# 2403_NUCLEO64.net
KiCad netlist of a schematic drawn in Altium Designer
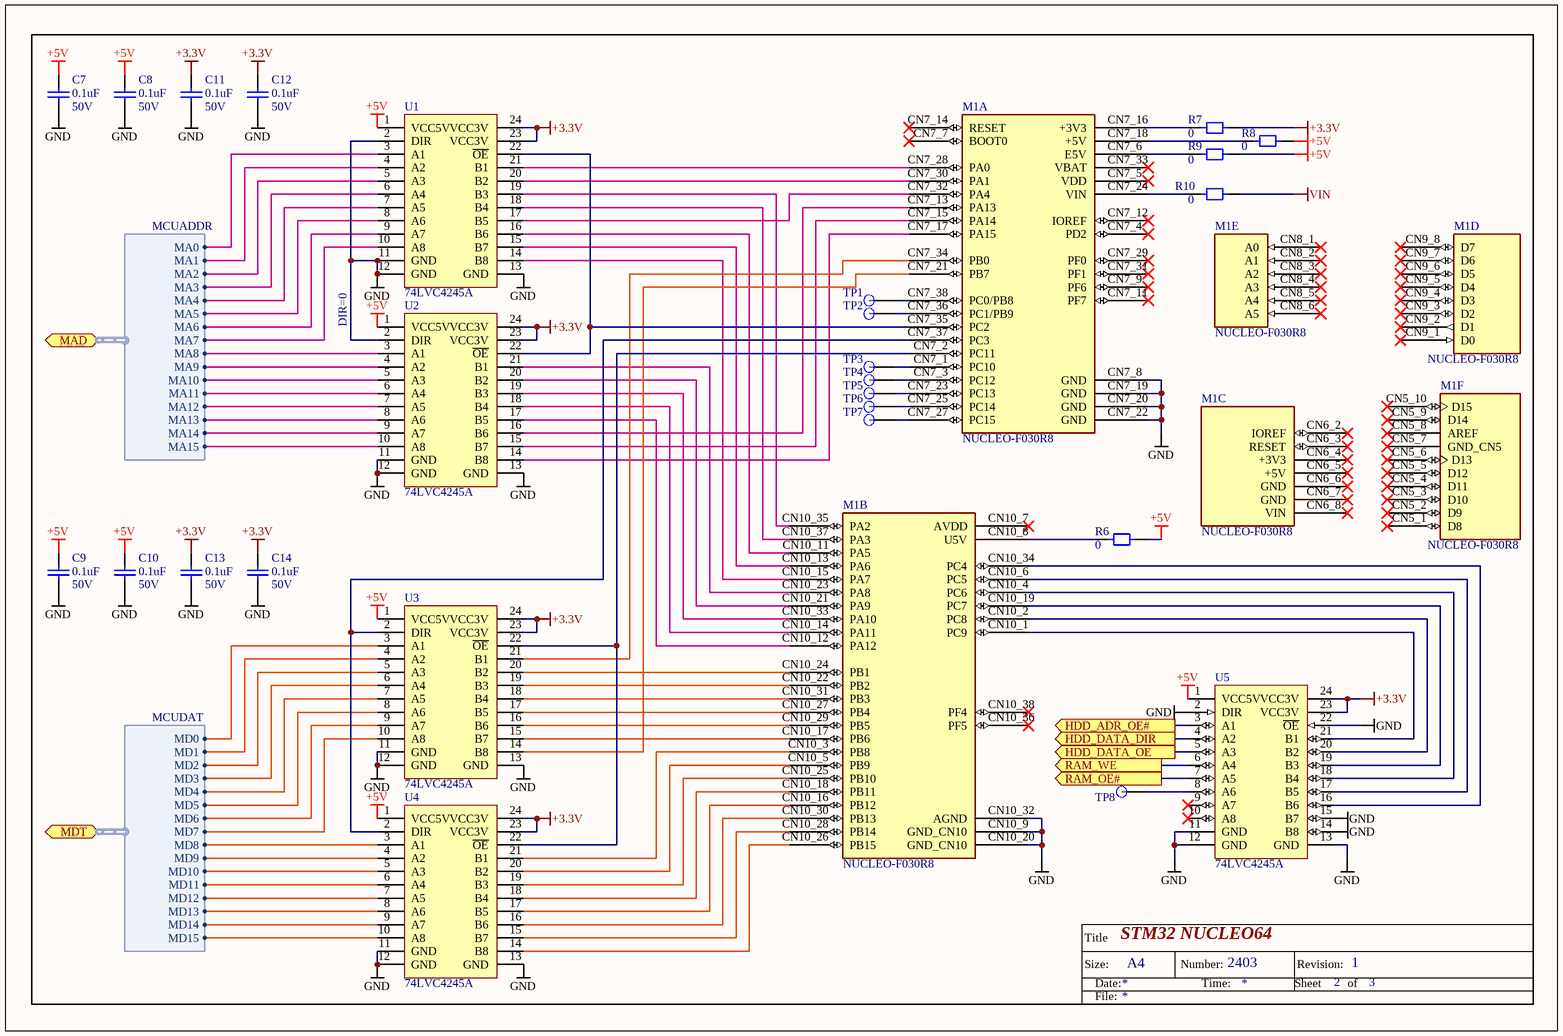
[diagram p0: 2403_NUCLEO64.SchDoc]

(export (version "E")
  (design (tool "Eeschema 10.0.6"))
  (components
    (comp (ref "C7")
      (value "0.1uF")
      (footprint "0805_CAPC2013X100N")
      (description "Capacitor SMD")
      (fields (field (name "RATED VOLTAGE") "50V") (field (name "PUBLISHER") "SY"))
      (libsource (lib "Prj24_Library") (part "Cap SMD"))
    )
    (comp (ref "C8")
      (value "0.1uF")
      (footprint "0805_CAPC2013X100N")
      (description "Capacitor SMD")
      (fields (field (name "RATED VOLTAGE") "50V") (field (name "PUBLISHER") "SY"))
      (libsource (lib "Prj24_Library") (part "Cap SMD"))
    )
    (comp (ref "C9")
      (value "0.1uF")
      (footprint "0805_CAPC2013X100N")
      (description "Capacitor SMD")
      (fields (field (name "RATED VOLTAGE") "50V") (field (name "PUBLISHER") "SY"))
      (libsource (lib "Prj24_Library") (part "Cap SMD"))
    )
    (comp (ref "C10")
      (value "0.1uF")
      (footprint "0805_CAPC2013X100N")
      (description "Capacitor SMD")
      (fields (field (name "RATED VOLTAGE") "50V") (field (name "PUBLISHER") "SY"))
      (libsource (lib "Prj24_Library") (part "Cap SMD"))
    )
    (comp (ref "C11")
      (value "0.1uF")
      (footprint "0805_CAPC2013X100N")
      (description "Capacitor SMD")
      (fields (field (name "RATED VOLTAGE") "50V") (field (name "PUBLISHER") "SY"))
      (libsource (lib "Prj24_Library") (part "Cap SMD"))
    )
    (comp (ref "C12")
      (value "0.1uF")
      (footprint "0805_CAPC2013X100N")
      (description "Capacitor SMD")
      (fields (field (name "RATED VOLTAGE") "50V") (field (name "PUBLISHER") "SY"))
      (libsource (lib "Prj24_Library") (part "Cap SMD"))
    )
    (comp (ref "C13")
      (value "0.1uF")
      (footprint "0805_CAPC2013X100N")
      (description "Capacitor SMD")
      (fields (field (name "RATED VOLTAGE") "50V") (field (name "PUBLISHER") "SY"))
      (libsource (lib "Prj24_Library") (part "Cap SMD"))
    )
    (comp (ref "C14")
      (value "0.1uF")
      (footprint "0805_CAPC2013X100N")
      (description "Capacitor SMD")
      (fields (field (name "RATED VOLTAGE") "50V") (field (name "PUBLISHER") "SY"))
      (libsource (lib "Prj24_Library") (part "Cap SMD"))
    )
    (comp (ref "M1")
      (value "NUCLEO-F030R8")
      (footprint "MODULE_NUCLEO-F030R8")
      (fields (field (name "MF") "STMicroelectronics") (field (name "PUBLISHER") "SY"))
      (libsource (lib "Prj24_Library") (part "NUCLEO-F030R8"))
    )
    (comp (ref "R6")
      (value "0")
      (footprint "0805_RESC2013X84N")
      (description "SMD Resistor")
      (fields (field (name "TOLERANCE") "5%") (field (name "POWER") "0.1W") (field (name "PUBLISHER") "SY"))
      (libsource (lib "Prj24_Library") (part "Resistor SMD L"))
    )
    (comp (ref "R7")
      (value "0")
      (footprint "0805_RESC2013X84N")
      (description "SMD Resistor")
      (fields (field (name "TOLERANCE") "5%") (field (name "POWER") "0.1W") (field (name "PUBLISHER") "SY"))
      (libsource (lib "Prj24_Library") (part "Resistor SMD L"))
    )
    (comp (ref "R8")
      (value "0")
      (footprint "0805_RESC2013X84N")
      (description "SMD Resistor")
      (fields (field (name "TOLERANCE") "5%") (field (name "POWER") "0.1W") (field (name "PUBLISHER") "SY"))
      (libsource (lib "Prj24_Library") (part "Resistor SMD L"))
    )
    (comp (ref "R9")
      (value "0")
      (footprint "0805_RESC2013X84N")
      (description "SMD Resistor")
      (fields (field (name "TOLERANCE") "5%") (field (name "POWER") "0.1W") (field (name "PUBLISHER") "SY"))
      (libsource (lib "Prj24_Library") (part "Resistor SMD L"))
    )
    (comp (ref "R10")
      (value "0")
      (footprint "0805_RESC2013X84N")
      (description "SMD Resistor")
      (fields (field (name "TOLERANCE") "5%") (field (name "POWER") "0.1W") (field (name "PUBLISHER") "SY"))
      (libsource (lib "Prj24_Library") (part "Resistor SMD L"))
    )
    (comp (ref "TP1")
      (value "TEST_POINT")
      (footprint "TEST2")
      (description "Test point")
      (fields (field (name "PUBLISHER") "SY"))
      (libsource (lib "Prj24_Library") (part "TEST_POINT"))
    )
    (comp (ref "TP2")
      (value "TEST_POINT")
      (footprint "TEST2")
      (description "Test point")
      (fields (field (name "PUBLISHER") "SY"))
      (libsource (lib "Prj24_Library") (part "TEST_POINT"))
    )
    (comp (ref "TP3")
      (value "TEST_POINT")
      (footprint "TEST2")
      (description "Test point")
      (fields (field (name "PUBLISHER") "SY"))
      (libsource (lib "Prj24_Library") (part "TEST_POINT"))
    )
    (comp (ref "TP4")
      (value "TEST_POINT")
      (footprint "TEST2")
      (description "Test point")
      (fields (field (name "PUBLISHER") "SY"))
      (libsource (lib "Prj24_Library") (part "TEST_POINT"))
    )
    (comp (ref "TP5")
      (value "TEST_POINT")
      (footprint "TEST2")
      (description "Test point")
      (fields (field (name "PUBLISHER") "SY"))
      (libsource (lib "Prj24_Library") (part "TEST_POINT"))
    )
    (comp (ref "TP6")
      (value "TEST_POINT")
      (footprint "TEST2")
      (description "Test point")
      (fields (field (name "PUBLISHER") "SY"))
      (libsource (lib "Prj24_Library") (part "TEST_POINT"))
    )
    (comp (ref "TP7")
      (value "TEST_POINT")
      (footprint "TEST2")
      (description "Test point")
      (fields (field (name "PUBLISHER") "SY"))
      (libsource (lib "Prj24_Library") (part "TEST_POINT"))
    )
    (comp (ref "TP8")
      (value "TEST_POINT")
      (footprint "TEST2")
      (description "Test point")
      (fields (field (name "PUBLISHER") "SY"))
      (libsource (lib "Prj24_Library") (part "TEST_POINT"))
    )
    (comp (ref "U1")
      (value "74LVC4245A")
      (footprint "SOIC127P1032X265-24N")
      (description "Octal Bus Transceiver and 3.3-V to 5-V Shifter\r\nWith 3-State Outputs")
      (fields (field (name "PUBLISHER") "SY") (field (name "SOURCE") "Renishaw MP12"))
      (libsource (lib "Prj24_Library") (part "74LVC4245A"))
    )
    (comp (ref "U2")
      (value "74LVC4245A")
      (footprint "SOIC127P1032X265-24N")
      (description "Octal Bus Transceiver and 3.3-V to 5-V Shifter\r\nWith 3-State Outputs")
      (fields (field (name "PUBLISHER") "SY") (field (name "SOURCE") "Renishaw MP12"))
      (libsource (lib "Prj24_Library") (part "74LVC4245A"))
    )
    (comp (ref "U3")
      (value "74LVC4245A")
      (footprint "SOIC127P1032X265-24N")
      (description "Octal Bus Transceiver and 3.3-V to 5-V Shifter\r\nWith 3-State Outputs")
      (fields (field (name "PUBLISHER") "SY") (field (name "SOURCE") "Renishaw MP12"))
      (libsource (lib "Prj24_Library") (part "74LVC4245A"))
    )
    (comp (ref "U4")
      (value "74LVC4245A")
      (footprint "SOIC127P1032X265-24N")
      (description "Octal Bus Transceiver and 3.3-V to 5-V Shifter\r\nWith 3-State Outputs")
      (fields (field (name "PUBLISHER") "SY") (field (name "SOURCE") "Renishaw MP12"))
      (libsource (lib "Prj24_Library") (part "74LVC4245A"))
    )
    (comp (ref "U5")
      (value "74LVC4245A")
      (footprint "SOIC127P1032X265-24N")
      (description "Octal Bus Transceiver and 3.3-V to 5-V Shifter\r\nWith 3-State Outputs")
      (fields (field (name "PUBLISHER") "SY") (field (name "SOURCE") "Renishaw MP12"))
      (libsource (lib "Prj24_Library") (part "74LVC4245A"))
    )
  )
  (nets
    (net (code "3") (name "+3.3V") (class "Default")
      (node (ref "C11") (pin "2") (pinfunction "2_2") (pintype "passive"))
      (node (ref "C12") (pin "2") (pinfunction "2_2") (pintype "passive"))
      (node (ref "C13") (pin "2") (pinfunction "2_2") (pintype "passive"))
      (node (ref "C14") (pin "2") (pinfunction "2_2") (pintype "passive"))
      (node (ref "R7") (pin "2") (pinfunction "2_2") (pintype "passive"))
      (node (ref "U1") (pin "23") (pinfunction "VCC3V_23") (pintype "passive"))
      (node (ref "U1") (pin "24") (pinfunction "VCC3V_24") (pintype "passive"))
      (node (ref "U2") (pin "23") (pinfunction "VCC3V_23") (pintype "passive"))
      (node (ref "U2") (pin "24") (pinfunction "VCC3V_24") (pintype "passive"))
      (node (ref "U3") (pin "23") (pinfunction "VCC3V_23") (pintype "passive"))
      (node (ref "U3") (pin "24") (pinfunction "VCC3V_24") (pintype "passive"))
      (node (ref "U4") (pin "23") (pinfunction "VCC3V_23") (pintype "passive"))
      (node (ref "U4") (pin "24") (pinfunction "VCC3V_24") (pintype "passive"))
      (node (ref "U5") (pin "23") (pinfunction "VCC3V_23") (pintype "passive"))
      (node (ref "U5") (pin "24") (pinfunction "VCC3V_24") (pintype "passive"))
    )
    (net (code "4") (name "+5V") (class "Default")
      (node (ref "C10") (pin "2") (pinfunction "2_2") (pintype "passive"))
      (node (ref "C7") (pin "2") (pinfunction "2_2") (pintype "passive"))
      (node (ref "C8") (pin "2") (pinfunction "2_2") (pintype "passive"))
      (node (ref "C9") (pin "2") (pinfunction "2_2") (pintype "passive"))
      (node (ref "R6") (pin "2") (pinfunction "2_2") (pintype "passive"))
      (node (ref "R8") (pin "2") (pinfunction "2_2") (pintype "passive"))
      (node (ref "R9") (pin "2") (pinfunction "2_2") (pintype "passive"))
      (node (ref "U1") (pin "1") (pinfunction "VCC5V_1") (pintype "passive"))
      (node (ref "U2") (pin "1") (pinfunction "VCC5V_1") (pintype "passive"))
      (node (ref "U3") (pin "1") (pinfunction "VCC5V_1") (pintype "passive"))
      (node (ref "U4") (pin "1") (pinfunction "VCC5V_1") (pintype "passive"))
      (node (ref "U5") (pin "1") (pinfunction "VCC5V_1") (pintype "passive"))
    )
    (net (code "5") (name "/HDD_ADR_OE#") (class "Default")
      (node (ref "U5") (pin "3") (pinfunction "A1_3") (pintype "passive"))
    )
    (net (code "6") (name "/HDD_DATA_DIR") (class "Default")
      (node (ref "U5") (pin "4") (pinfunction "A2_4") (pintype "passive"))
    )
    (net (code "7") (name "/HDD_DATA_OE") (class "Default")
      (node (ref "U5") (pin "5") (pinfunction "A3_5") (pintype "passive"))
    )
    (net (code "8") (name "/MA0") (class "Default")
      (node (ref "U1") (pin "3") (pinfunction "A1_3") (pintype "passive"))
    )
    (net (code "9") (name "/MA1") (class "Default")
      (node (ref "U1") (pin "4") (pinfunction "A2_4") (pintype "passive"))
    )
    (net (code "10") (name "/MA2") (class "Default")
      (node (ref "U1") (pin "5") (pinfunction "A3_5") (pintype "passive"))
    )
    (net (code "11") (name "/MA3") (class "Default")
      (node (ref "U1") (pin "6") (pinfunction "A4_6") (pintype "passive"))
    )
    (net (code "12") (name "/MA4") (class "Default")
      (node (ref "U1") (pin "7") (pinfunction "A5_7") (pintype "passive"))
    )
    (net (code "13") (name "/MA5") (class "Default")
      (node (ref "U1") (pin "8") (pinfunction "A6_8") (pintype "passive"))
    )
    (net (code "14") (name "/MA6") (class "Default")
      (node (ref "U1") (pin "9") (pinfunction "A7_9") (pintype "passive"))
    )
    (net (code "15") (name "/MA7") (class "Default")
      (node (ref "U1") (pin "10") (pinfunction "A8_10") (pintype "passive"))
    )
    (net (code "16") (name "/MA8") (class "Default")
      (node (ref "U2") (pin "3") (pinfunction "A1_3") (pintype "passive"))
    )
    (net (code "17") (name "/MA9") (class "Default")
      (node (ref "U2") (pin "4") (pinfunction "A2_4") (pintype "passive"))
    )
    (net (code "18") (name "/MA10") (class "Default")
      (node (ref "U2") (pin "5") (pinfunction "A3_5") (pintype "passive"))
    )
    (net (code "19") (name "/MA11") (class "Default")
      (node (ref "U2") (pin "6") (pinfunction "A4_6") (pintype "passive"))
    )
    (net (code "20") (name "/MA12") (class "Default")
      (node (ref "U2") (pin "7") (pinfunction "A5_7") (pintype "passive"))
    )
    (net (code "21") (name "/MA13") (class "Default")
      (node (ref "U2") (pin "8") (pinfunction "A6_8") (pintype "passive"))
    )
    (net (code "22") (name "/MA14") (class "Default")
      (node (ref "U2") (pin "9") (pinfunction "A7_9") (pintype "passive"))
    )
    (net (code "23") (name "/MA15") (class "Default")
      (node (ref "U2") (pin "10") (pinfunction "A8_10") (pintype "passive"))
    )
    (net (code "24") (name "/MD0") (class "Default")
      (node (ref "U3") (pin "3") (pinfunction "A1_3") (pintype "passive"))
    )
    (net (code "25") (name "/MD1") (class "Default")
      (node (ref "U3") (pin "4") (pinfunction "A2_4") (pintype "passive"))
    )
    (net (code "26") (name "/MD2") (class "Default")
      (node (ref "U3") (pin "5") (pinfunction "A3_5") (pintype "passive"))
    )
    (net (code "27") (name "/MD3") (class "Default")
      (node (ref "U3") (pin "6") (pinfunction "A4_6") (pintype "passive"))
    )
    (net (code "28") (name "/MD4") (class "Default")
      (node (ref "U3") (pin "7") (pinfunction "A5_7") (pintype "passive"))
    )
    (net (code "29") (name "/MD5") (class "Default")
      (node (ref "U3") (pin "8") (pinfunction "A6_8") (pintype "passive"))
    )
    (net (code "30") (name "/MD6") (class "Default")
      (node (ref "U3") (pin "9") (pinfunction "A7_9") (pintype "passive"))
    )
    (net (code "31") (name "/MD7") (class "Default")
      (node (ref "U3") (pin "10") (pinfunction "A8_10") (pintype "passive"))
    )
    (net (code "32") (name "/MD8") (class "Default")
      (node (ref "U4") (pin "3") (pinfunction "A1_3") (pintype "passive"))
    )
    (net (code "33") (name "/MD9") (class "Default")
      (node (ref "U4") (pin "4") (pinfunction "A2_4") (pintype "passive"))
    )
    (net (code "34") (name "/MD10") (class "Default")
      (node (ref "U4") (pin "5") (pinfunction "A3_5") (pintype "passive"))
    )
    (net (code "35") (name "/MD11") (class "Default")
      (node (ref "U4") (pin "6") (pinfunction "A4_6") (pintype "passive"))
    )
    (net (code "36") (name "/MD12") (class "Default")
      (node (ref "U4") (pin "7") (pinfunction "A5_7") (pintype "passive"))
    )
    (net (code "37") (name "/MD13") (class "Default")
      (node (ref "U4") (pin "8") (pinfunction "A6_8") (pintype "passive"))
    )
    (net (code "38") (name "/MD14") (class "Default")
      (node (ref "U4") (pin "9") (pinfunction "A7_9") (pintype "passive"))
    )
    (net (code "39") (name "/MD15") (class "Default")
      (node (ref "U4") (pin "10") (pinfunction "A8_10") (pintype "passive"))
    )
    (net (code "40") (name "/RAM_OE#") (class "Default")
      (node (ref "U5") (pin "7") (pinfunction "A5_7") (pintype "passive"))
    )
    (net (code "41") (name "/RAM_WE") (class "Default")
      (node (ref "U5") (pin "6") (pinfunction "A4_6") (pintype "passive"))
    )
    (net (code "44") (name "GND") (class "Default")
      (node (ref "C10") (pin "1") (pinfunction "1_1") (pintype "passive"))
      (node (ref "C11") (pin "1") (pinfunction "1_1") (pintype "passive"))
      (node (ref "C12") (pin "1") (pinfunction "1_1") (pintype "passive"))
      (node (ref "C13") (pin "1") (pinfunction "1_1") (pintype "passive"))
      (node (ref "C14") (pin "1") (pinfunction "1_1") (pintype "passive"))
      (node (ref "C7") (pin "1") (pinfunction "1_1") (pintype "passive"))
      (node (ref "C8") (pin "1") (pinfunction "1_1") (pintype "passive"))
      (node (ref "C9") (pin "1") (pinfunction "1_1") (pintype "passive"))
      (node (ref "M1") (pin "CN10_20") (pinfunction "GND_CN10_CN10_20") (pintype "power_in"))
      (node (ref "M1") (pin "CN10_32") (pinfunction "AGND_CN10_32") (pintype "power_in"))
      (node (ref "M1") (pin "CN10_9") (pinfunction "GND_CN10_CN10_9") (pintype "power_in"))
      (node (ref "M1") (pin "CN7_19") (pinfunction "GND_CN7_19") (pintype "power_in"))
      (node (ref "M1") (pin "CN7_20") (pinfunction "GND_CN7_20") (pintype "power_in"))
      (node (ref "M1") (pin "CN7_22") (pinfunction "GND_CN7_22") (pintype "power_in"))
      (node (ref "M1") (pin "CN7_8") (pinfunction "GND_CN7_8") (pintype "power_in"))
      (node (ref "U1") (pin "11") (pinfunction "GND_11") (pintype "passive"))
      (node (ref "U1") (pin "12") (pinfunction "GND_12") (pintype "passive"))
      (node (ref "U1") (pin "13") (pinfunction "GND_13") (pintype "passive"))
      (node (ref "U1") (pin "2") (pinfunction "DIR_2") (pintype "passive"))
      (node (ref "U2") (pin "11") (pinfunction "GND_11") (pintype "passive"))
      (node (ref "U2") (pin "12") (pinfunction "GND_12") (pintype "passive"))
      (node (ref "U2") (pin "13") (pinfunction "GND_13") (pintype "passive"))
      (node (ref "U2") (pin "2") (pinfunction "DIR_2") (pintype "passive"))
      (node (ref "U3") (pin "11") (pinfunction "GND_11") (pintype "passive"))
      (node (ref "U3") (pin "12") (pinfunction "GND_12") (pintype "passive"))
      (node (ref "U3") (pin "13") (pinfunction "GND_13") (pintype "passive"))
      (node (ref "U4") (pin "11") (pinfunction "GND_11") (pintype "passive"))
      (node (ref "U4") (pin "12") (pinfunction "GND_12") (pintype "passive"))
      (node (ref "U4") (pin "13") (pinfunction "GND_13") (pintype "passive"))
      (node (ref "U5") (pin "11") (pinfunction "GND_11") (pintype "passive"))
      (node (ref "U5") (pin "12") (pinfunction "GND_12") (pintype "passive"))
      (node (ref "U5") (pin "13") (pinfunction "GND_13") (pintype "passive"))
      (node (ref "U5") (pin "14") (pinfunction "B8_14") (pintype "passive"))
      (node (ref "U5") (pin "15") (pinfunction "B7_15") (pintype "passive"))
      (node (ref "U5") (pin "2") (pinfunction "DIR_2") (pintype "passive"))
      (node (ref "U5") (pin "22") (pinfunction "~{OE}_22") (pintype "passive"))
    )
    (net (code "45") (name "Net-(M1A-+3V3)") (class "Default")
      (node (ref "M1") (pin "CN7_16") (pinfunction "+3V3_CN7_16") (pintype "power_in"))
      (node (ref "R7") (pin "1") (pinfunction "1_1") (pintype "passive"))
    )
    (net (code "46") (name "Net-(M1A-+5V)") (class "Default")
      (node (ref "M1") (pin "CN7_18") (pinfunction "+5V_CN7_18") (pintype "power_in"))
      (node (ref "R8") (pin "1") (pinfunction "1_1") (pintype "passive"))
    )
    (net (code "47") (name "Net-(M1A-E5V)") (class "Default")
      (node (ref "M1") (pin "CN7_6") (pinfunction "E5V_CN7_6") (pintype "power_in"))
      (node (ref "R9") (pin "1") (pinfunction "1_1") (pintype "passive"))
    )
    (net (code "48") (name "Net-(M1A-PA0)") (class "Default")
      (node (ref "M1") (pin "CN7_28") (pinfunction "PA0_CN7_28") (pintype "bidirectional"))
      (node (ref "U1") (pin "21") (pinfunction "B1_21") (pintype "passive"))
    )
    (net (code "49") (name "Net-(M1A-PA1)") (class "Default")
      (node (ref "M1") (pin "CN7_30") (pinfunction "PA1_CN7_30") (pintype "bidirectional"))
      (node (ref "U1") (pin "20") (pinfunction "B2_20") (pintype "passive"))
    )
    (net (code "50") (name "Net-(M1A-PA4)") (class "Default")
      (node (ref "M1") (pin "CN7_32") (pinfunction "PA4_CN7_32") (pintype "bidirectional"))
      (node (ref "U1") (pin "17") (pinfunction "B5_17") (pintype "passive"))
    )
    (net (code "51") (name "Net-(M1A-PA13)") (class "Default")
      (node (ref "M1") (pin "CN7_13") (pinfunction "PA13_CN7_13") (pintype "bidirectional"))
      (node (ref "U2") (pin "16") (pinfunction "B6_16") (pintype "passive"))
    )
    (net (code "52") (name "Net-(M1A-PA14)") (class "Default")
      (node (ref "M1") (pin "CN7_15") (pinfunction "PA14_CN7_15") (pintype "bidirectional"))
      (node (ref "U2") (pin "15") (pinfunction "B7_15") (pintype "passive"))
    )
    (net (code "53") (name "Net-(M1A-PA15)") (class "Default")
      (node (ref "M1") (pin "CN7_17") (pinfunction "PA15_CN7_17") (pintype "bidirectional"))
      (node (ref "U2") (pin "14") (pinfunction "B8_14") (pintype "passive"))
    )
    (net (code "54") (name "Net-(M1A-PB0)") (class "Default")
      (node (ref "M1") (pin "CN7_34") (pinfunction "PB0_CN7_34") (pintype "bidirectional"))
      (node (ref "U3") (pin "21") (pinfunction "B1_21") (pintype "passive"))
    )
    (net (code "55") (name "Net-(M1A-PB7)") (class "Default")
      (node (ref "M1") (pin "CN7_21") (pinfunction "PB7_CN7_21") (pintype "bidirectional"))
      (node (ref "U3") (pin "14") (pinfunction "B8_14") (pintype "passive"))
    )
    (net (code "56") (name "Net-(M1A-PC0{slash}PB8)") (class "Default")
      (node (ref "M1") (pin "CN7_38") (pinfunction "PC0/PB8_CN7_38") (pintype "bidirectional"))
      (node (ref "TP1") (pin "1") (pinfunction "T_1") (pintype "passive"))
    )
    (net (code "57") (name "Net-(M1A-PC1{slash}PB9)") (class "Default")
      (node (ref "M1") (pin "CN7_36") (pinfunction "PC1/PB9_CN7_36") (pintype "bidirectional"))
      (node (ref "TP2") (pin "1") (pinfunction "T_1") (pintype "passive"))
    )
    (net (code "58") (name "Net-(M1A-PC2)") (class "Default")
      (node (ref "M1") (pin "CN7_35") (pinfunction "PC2_CN7_35") (pintype "bidirectional"))
      (node (ref "U1") (pin "22") (pinfunction "~{OE}_22") (pintype "passive"))
      (node (ref "U2") (pin "22") (pinfunction "~{OE}_22") (pintype "passive"))
    )
    (net (code "59") (name "Net-(M1A-PC3)") (class "Default")
      (node (ref "M1") (pin "CN7_37") (pinfunction "PC3_CN7_37") (pintype "bidirectional"))
      (node (ref "U3") (pin "2") (pinfunction "DIR_2") (pintype "passive"))
      (node (ref "U4") (pin "2") (pinfunction "DIR_2") (pintype "passive"))
    )
    (net (code "60") (name "Net-(M1A-PC10)") (class "Default")
      (node (ref "M1") (pin "CN7_1") (pinfunction "PC10_CN7_1") (pintype "bidirectional"))
      (node (ref "TP3") (pin "1") (pinfunction "T_1") (pintype "passive"))
    )
    (net (code "61") (name "Net-(M1A-PC11)") (class "Default")
      (node (ref "M1") (pin "CN7_2") (pinfunction "PC11_CN7_2") (pintype "bidirectional"))
      (node (ref "U3") (pin "22") (pinfunction "~{OE}_22") (pintype "passive"))
      (node (ref "U4") (pin "22") (pinfunction "~{OE}_22") (pintype "passive"))
    )
    (net (code "62") (name "Net-(M1A-PC12)") (class "Default")
      (node (ref "M1") (pin "CN7_3") (pinfunction "PC12_CN7_3") (pintype "bidirectional"))
      (node (ref "TP4") (pin "1") (pinfunction "T_1") (pintype "passive"))
    )
    (net (code "63") (name "Net-(M1A-PC13)") (class "Default")
      (node (ref "M1") (pin "CN7_23") (pinfunction "PC13_CN7_23") (pintype "bidirectional"))
      (node (ref "TP5") (pin "1") (pinfunction "T_1") (pintype "passive"))
    )
    (net (code "64") (name "Net-(M1A-PC14)") (class "Default")
      (node (ref "M1") (pin "CN7_25") (pinfunction "PC14_CN7_25") (pintype "bidirectional"))
      (node (ref "TP6") (pin "1") (pinfunction "T_1") (pintype "passive"))
    )
    (net (code "65") (name "Net-(M1A-PC15)") (class "Default")
      (node (ref "M1") (pin "CN7_27") (pinfunction "PC15_CN7_27") (pintype "bidirectional"))
      (node (ref "TP7") (pin "1") (pinfunction "T_1") (pintype "passive"))
    )
    (net (code "66") (name "Net-(M1A-VIN)") (class "Default")
      (node (ref "M1") (pin "CN7_24") (pinfunction "VIN_CN7_24") (pintype "power_in"))
      (node (ref "R10") (pin "1") (pinfunction "1_1") (pintype "passive"))
    )
    (net (code "67") (name "Net-(M1B-PA2)") (class "Default")
      (node (ref "M1") (pin "CN10_35") (pinfunction "PA2_CN10_35") (pintype "bidirectional"))
      (node (ref "U1") (pin "19") (pinfunction "B3_19") (pintype "passive"))
    )
    (net (code "68") (name "Net-(M1B-PA3)") (class "Default")
      (node (ref "M1") (pin "CN10_37") (pinfunction "PA3_CN10_37") (pintype "bidirectional"))
      (node (ref "U1") (pin "18") (pinfunction "B4_18") (pintype "passive"))
    )
    (net (code "69") (name "Net-(M1B-PA5)") (class "Default")
      (node (ref "M1") (pin "CN10_11") (pinfunction "PA5_CN10_11") (pintype "bidirectional"))
      (node (ref "U1") (pin "16") (pinfunction "B6_16") (pintype "passive"))
    )
    (net (code "70") (name "Net-(M1B-PA6)") (class "Default")
      (node (ref "M1") (pin "CN10_13") (pinfunction "PA6_CN10_13") (pintype "bidirectional"))
      (node (ref "U1") (pin "15") (pinfunction "B7_15") (pintype "passive"))
    )
    (net (code "71") (name "Net-(M1B-PA7)") (class "Default")
      (node (ref "M1") (pin "CN10_15") (pinfunction "PA7_CN10_15") (pintype "bidirectional"))
      (node (ref "U1") (pin "14") (pinfunction "B8_14") (pintype "passive"))
    )
    (net (code "72") (name "Net-(M1B-PA8)") (class "Default")
      (node (ref "M1") (pin "CN10_23") (pinfunction "PA8_CN10_23") (pintype "bidirectional"))
      (node (ref "U2") (pin "21") (pinfunction "B1_21") (pintype "passive"))
    )
    (net (code "73") (name "Net-(M1B-PA9)") (class "Default")
      (node (ref "M1") (pin "CN10_21") (pinfunction "PA9_CN10_21") (pintype "bidirectional"))
      (node (ref "U2") (pin "20") (pinfunction "B2_20") (pintype "passive"))
    )
    (net (code "74") (name "Net-(M1B-PA10)") (class "Default")
      (node (ref "M1") (pin "CN10_33") (pinfunction "PA10_CN10_33") (pintype "bidirectional"))
      (node (ref "U2") (pin "19") (pinfunction "B3_19") (pintype "passive"))
    )
    (net (code "75") (name "Net-(M1B-PA11)") (class "Default")
      (node (ref "M1") (pin "CN10_14") (pinfunction "PA11_CN10_14") (pintype "bidirectional"))
      (node (ref "U2") (pin "18") (pinfunction "B4_18") (pintype "passive"))
    )
    (net (code "76") (name "Net-(M1B-PA12)") (class "Default")
      (node (ref "M1") (pin "CN10_12") (pinfunction "PA12_CN10_12") (pintype "bidirectional"))
      (node (ref "U2") (pin "17") (pinfunction "B5_17") (pintype "passive"))
    )
    (net (code "77") (name "Net-(M1B-PB1)") (class "Default")
      (node (ref "M1") (pin "CN10_24") (pinfunction "PB1_CN10_24") (pintype "bidirectional"))
      (node (ref "U3") (pin "20") (pinfunction "B2_20") (pintype "passive"))
    )
    (net (code "78") (name "Net-(M1B-PB2)") (class "Default")
      (node (ref "M1") (pin "CN10_22") (pinfunction "PB2_CN10_22") (pintype "bidirectional"))
      (node (ref "U3") (pin "19") (pinfunction "B3_19") (pintype "passive"))
    )
    (net (code "79") (name "Net-(M1B-PB3)") (class "Default")
      (node (ref "M1") (pin "CN10_31") (pinfunction "PB3_CN10_31") (pintype "bidirectional"))
      (node (ref "U3") (pin "18") (pinfunction "B4_18") (pintype "passive"))
    )
    (net (code "80") (name "Net-(M1B-PB4)") (class "Default")
      (node (ref "M1") (pin "CN10_27") (pinfunction "PB4_CN10_27") (pintype "bidirectional"))
      (node (ref "U3") (pin "17") (pinfunction "B5_17") (pintype "passive"))
    )
    (net (code "81") (name "Net-(M1B-PB5)") (class "Default")
      (node (ref "M1") (pin "CN10_29") (pinfunction "PB5_CN10_29") (pintype "bidirectional"))
      (node (ref "U3") (pin "16") (pinfunction "B6_16") (pintype "passive"))
    )
    (net (code "82") (name "Net-(M1B-PB6)") (class "Default")
      (node (ref "M1") (pin "CN10_17") (pinfunction "PB6_CN10_17") (pintype "bidirectional"))
      (node (ref "U3") (pin "15") (pinfunction "B7_15") (pintype "passive"))
    )
    (net (code "83") (name "Net-(M1B-PB8)") (class "Default")
      (node (ref "M1") (pin "CN10_3") (pinfunction "PB8_CN10_3") (pintype "bidirectional"))
      (node (ref "U4") (pin "21") (pinfunction "B1_21") (pintype "passive"))
    )
    (net (code "84") (name "Net-(M1B-PB9)") (class "Default")
      (node (ref "M1") (pin "CN10_5") (pinfunction "PB9_CN10_5") (pintype "bidirectional"))
      (node (ref "U4") (pin "20") (pinfunction "B2_20") (pintype "passive"))
    )
    (net (code "85") (name "Net-(M1B-PB10)") (class "Default")
      (node (ref "M1") (pin "CN10_25") (pinfunction "PB10_CN10_25") (pintype "bidirectional"))
      (node (ref "U4") (pin "19") (pinfunction "B3_19") (pintype "passive"))
    )
    (net (code "86") (name "Net-(M1B-PB11)") (class "Default")
      (node (ref "M1") (pin "CN10_18") (pinfunction "PB11_CN10_18") (pintype "bidirectional"))
      (node (ref "U4") (pin "18") (pinfunction "B4_18") (pintype "passive"))
    )
    (net (code "87") (name "Net-(M1B-PB12)") (class "Default")
      (node (ref "M1") (pin "CN10_16") (pinfunction "PB12_CN10_16") (pintype "bidirectional"))
      (node (ref "U4") (pin "17") (pinfunction "B5_17") (pintype "passive"))
    )
    (net (code "88") (name "Net-(M1B-PB13)") (class "Default")
      (node (ref "M1") (pin "CN10_30") (pinfunction "PB13_CN10_30") (pintype "bidirectional"))
      (node (ref "U4") (pin "16") (pinfunction "B6_16") (pintype "passive"))
    )
    (net (code "89") (name "Net-(M1B-PB14)") (class "Default")
      (node (ref "M1") (pin "CN10_28") (pinfunction "PB14_CN10_28") (pintype "bidirectional"))
      (node (ref "U4") (pin "15") (pinfunction "B7_15") (pintype "passive"))
    )
    (net (code "90") (name "Net-(M1B-PB15)") (class "Default")
      (node (ref "M1") (pin "CN10_26") (pinfunction "PB15_CN10_26") (pintype "bidirectional"))
      (node (ref "U4") (pin "14") (pinfunction "B8_14") (pintype "passive"))
    )
    (net (code "91") (name "Net-(M1B-PC4)") (class "Default")
      (node (ref "M1") (pin "CN10_34") (pinfunction "PC4_CN10_34") (pintype "bidirectional"))
      (node (ref "U5") (pin "16") (pinfunction "B6_16") (pintype "passive"))
    )
    (net (code "92") (name "Net-(M1B-PC5)") (class "Default")
      (node (ref "M1") (pin "CN10_6") (pinfunction "PC5_CN10_6") (pintype "bidirectional"))
      (node (ref "U5") (pin "17") (pinfunction "B5_17") (pintype "passive"))
    )
    (net (code "93") (name "Net-(M1B-PC6)") (class "Default")
      (node (ref "M1") (pin "CN10_4") (pinfunction "PC6_CN10_4") (pintype "bidirectional"))
      (node (ref "U5") (pin "18") (pinfunction "B4_18") (pintype "passive"))
    )
    (net (code "94") (name "Net-(M1B-PC7)") (class "Default")
      (node (ref "M1") (pin "CN10_19") (pinfunction "PC7_CN10_19") (pintype "bidirectional"))
      (node (ref "U5") (pin "19") (pinfunction "B3_19") (pintype "passive"))
    )
    (net (code "95") (name "Net-(M1B-PC8)") (class "Default")
      (node (ref "M1") (pin "CN10_2") (pinfunction "PC8_CN10_2") (pintype "bidirectional"))
      (node (ref "U5") (pin "20") (pinfunction "B2_20") (pintype "passive"))
    )
    (net (code "96") (name "Net-(M1B-PC9)") (class "Default")
      (node (ref "M1") (pin "CN10_1") (pinfunction "PC9_CN10_1") (pintype "bidirectional"))
      (node (ref "U5") (pin "21") (pinfunction "B1_21") (pintype "passive"))
    )
    (net (code "97") (name "Net-(M1B-U5V)") (class "Default")
      (node (ref "M1") (pin "CN10_8") (pinfunction "U5V_CN10_8") (pintype "power_in"))
      (node (ref "R6") (pin "1") (pinfunction "1_1") (pintype "passive"))
    )
    (net (code "98") (name "Net-(TP8-T)") (class "Default")
      (node (ref "TP8") (pin "1") (pinfunction "T_1") (pintype "passive"))
      (node (ref "U5") (pin "8") (pinfunction "A6_8") (pintype "passive"))
    )
    (net (code "99") (name "VIN") (class "Default")
      (node (ref "R10") (pin "2") (pinfunction "2_2") (pintype "passive"))
    )
    (net (code "100") (name "unconnected-(M1A-BOOT0-PadCN7_7)") (class "Default")
      (node (ref "M1") (pin "CN7_7") (pinfunction "BOOT0_CN7_7") (pintype "bidirectional+no_connect"))
    )
    (net (code "101") (name "unconnected-(M1A-IOREF-PadCN7_12)") (class "Default")
      (node (ref "M1") (pin "CN7_12") (pinfunction "IOREF_CN7_12") (pintype "bidirectional+no_connect"))
    )
    (net (code "102") (name "unconnected-(M1A-PD2-PadCN7_4)") (class "Default")
      (node (ref "M1") (pin "CN7_4") (pinfunction "PD2_CN7_4") (pintype "bidirectional+no_connect"))
    )
    (net (code "103") (name "unconnected-(M1A-PF0-PadCN7_29)") (class "Default")
      (node (ref "M1") (pin "CN7_29") (pinfunction "PF0_CN7_29") (pintype "bidirectional+no_connect"))
    )
    (net (code "104") (name "unconnected-(M1A-PF1-PadCN7_31)") (class "Default")
      (node (ref "M1") (pin "CN7_31") (pinfunction "PF1_CN7_31") (pintype "bidirectional+no_connect"))
    )
    (net (code "105") (name "unconnected-(M1A-PF6-PadCN7_9)") (class "Default")
      (node (ref "M1") (pin "CN7_9") (pinfunction "PF6_CN7_9") (pintype "bidirectional+no_connect"))
    )
    (net (code "106") (name "unconnected-(M1A-PF7-PadCN7_11)") (class "Default")
      (node (ref "M1") (pin "CN7_11") (pinfunction "PF7_CN7_11") (pintype "bidirectional+no_connect"))
    )
    (net (code "107") (name "unconnected-(M1A-RESET-PadCN7_14)") (class "Default")
      (node (ref "M1") (pin "CN7_14") (pinfunction "RESET_CN7_14") (pintype "bidirectional+no_connect"))
    )
    (net (code "108") (name "unconnected-(M1A-VBAT-PadCN7_33)") (class "Default")
      (node (ref "M1") (pin "CN7_33") (pinfunction "VBAT_CN7_33") (pintype "power_in+no_connect"))
    )
    (net (code "109") (name "unconnected-(M1A-VDD-PadCN7_5)") (class "Default")
      (node (ref "M1") (pin "CN7_5") (pinfunction "VDD_CN7_5") (pintype "power_in+no_connect"))
    )
    (net (code "110") (name "unconnected-(M1B-AVDD-PadCN10_7)") (class "Default")
      (node (ref "M1") (pin "CN10_7") (pinfunction "AVDD_CN10_7") (pintype "power_in+no_connect"))
    )
    (net (code "111") (name "unconnected-(M1B-PF4-PadCN10_38)") (class "Default")
      (node (ref "M1") (pin "CN10_38") (pinfunction "PF4_CN10_38") (pintype "bidirectional+no_connect"))
    )
    (net (code "112") (name "unconnected-(M1B-PF5-PadCN10_36)") (class "Default")
      (node (ref "M1") (pin "CN10_36") (pinfunction "PF5_CN10_36") (pintype "bidirectional+no_connect"))
    )
    (net (code "113") (name "unconnected-(M1C-+3V3-PadCN6_4)") (class "Default")
      (node (ref "M1") (pin "CN6_4") (pinfunction "+3V3_CN6_4") (pintype "power_in+no_connect"))
    )
    (net (code "114") (name "unconnected-(M1C-+5V-PadCN6_5)") (class "Default")
      (node (ref "M1") (pin "CN6_5") (pinfunction "+5V_CN6_5") (pintype "power_in+no_connect"))
    )
    (net (code "115") (name "unconnected-(M1C-GND-PadCN6_6)") (class "Default")
      (node (ref "M1") (pin "CN6_6") (pinfunction "GND_CN6_6") (pintype "power_in+no_connect"))
    )
    (net (code "116") (name "unconnected-(M1C-GND-PadCN6_7)") (class "Default")
      (node (ref "M1") (pin "CN6_7") (pinfunction "GND_CN6_7") (pintype "power_in+no_connect"))
    )
    (net (code "117") (name "unconnected-(M1C-IOREF-PadCN6_2)") (class "Default")
      (node (ref "M1") (pin "CN6_2") (pinfunction "IOREF_CN6_2") (pintype "bidirectional+no_connect"))
    )
    (net (code "118") (name "unconnected-(M1C-RESET-PadCN6_3)") (class "Default")
      (node (ref "M1") (pin "CN6_3") (pinfunction "RESET_CN6_3") (pintype "bidirectional+no_connect"))
    )
    (net (code "119") (name "unconnected-(M1C-VIN-PadCN6_8)") (class "Default")
      (node (ref "M1") (pin "CN6_8") (pinfunction "VIN_CN6_8") (pintype "power_in+no_connect"))
    )
    (net (code "120") (name "unconnected-(M1D-D0-PadCN9_1)") (class "Default")
      (node (ref "M1") (pin "CN9_1") (pinfunction "D0_CN9_1") (pintype "input+no_connect"))
    )
    (net (code "121") (name "unconnected-(M1D-D1-PadCN9_2)") (class "Default")
      (node (ref "M1") (pin "CN9_2") (pinfunction "D1_CN9_2") (pintype "output+no_connect"))
    )
    (net (code "122") (name "unconnected-(M1D-D2-PadCN9_3)") (class "Default")
      (node (ref "M1") (pin "CN9_3") (pinfunction "D2_CN9_3") (pintype "bidirectional+no_connect"))
    )
    (net (code "123") (name "unconnected-(M1D-D3-PadCN9_4)") (class "Default")
      (node (ref "M1") (pin "CN9_4") (pinfunction "D3_CN9_4") (pintype "bidirectional+no_connect"))
    )
    (net (code "124") (name "unconnected-(M1D-D4-PadCN9_5)") (class "Default")
      (node (ref "M1") (pin "CN9_5") (pinfunction "D4_CN9_5") (pintype "bidirectional+no_connect"))
    )
    (net (code "125") (name "unconnected-(M1D-D5-PadCN9_6)") (class "Default")
      (node (ref "M1") (pin "CN9_6") (pinfunction "D5_CN9_6") (pintype "bidirectional+no_connect"))
    )
    (net (code "126") (name "unconnected-(M1D-D6-PadCN9_7)") (class "Default")
      (node (ref "M1") (pin "CN9_7") (pinfunction "D6_CN9_7") (pintype "bidirectional+no_connect"))
    )
    (net (code "127") (name "unconnected-(M1D-D7-PadCN9_8)") (class "Default")
      (node (ref "M1") (pin "CN9_8") (pinfunction "D7_CN9_8") (pintype "bidirectional+no_connect"))
    )
    (net (code "128") (name "unconnected-(M1E-A0-PadCN8_1)") (class "Default")
      (node (ref "M1") (pin "CN8_1") (pinfunction "A0_CN8_1") (pintype "input+no_connect"))
    )
    (net (code "129") (name "unconnected-(M1E-A1-PadCN8_2)") (class "Default")
      (node (ref "M1") (pin "CN8_2") (pinfunction "A1_CN8_2") (pintype "input+no_connect"))
    )
    (net (code "130") (name "unconnected-(M1E-A2-PadCN8_3)") (class "Default")
      (node (ref "M1") (pin "CN8_3") (pinfunction "A2_CN8_3") (pintype "input+no_connect"))
    )
    (net (code "131") (name "unconnected-(M1E-A3-PadCN8_4)") (class "Default")
      (node (ref "M1") (pin "CN8_4") (pinfunction "A3_CN8_4") (pintype "input+no_connect"))
    )
    (net (code "132") (name "unconnected-(M1E-A4-PadCN8_5)") (class "Default")
      (node (ref "M1") (pin "CN8_5") (pinfunction "A4_CN8_5") (pintype "input+no_connect"))
    )
    (net (code "133") (name "unconnected-(M1E-A5-PadCN8_6)") (class "Default")
      (node (ref "M1") (pin "CN8_6") (pinfunction "A5_CN8_6") (pintype "input+no_connect"))
    )
    (net (code "134") (name "unconnected-(M1F-AREF-PadCN5_8)") (class "Default")
      (node (ref "M1") (pin "CN5_8") (pinfunction "AREF_CN5_8") (pintype "power_in+no_connect"))
    )
    (net (code "135") (name "unconnected-(M1F-D8-PadCN5_1)") (class "Default")
      (node (ref "M1") (pin "CN5_1") (pinfunction "D8_CN5_1") (pintype "bidirectional+no_connect"))
    )
    (net (code "136") (name "unconnected-(M1F-D9-PadCN5_2)") (class "Default")
      (node (ref "M1") (pin "CN5_2") (pinfunction "D9_CN5_2") (pintype "bidirectional+no_connect"))
    )
    (net (code "137") (name "unconnected-(M1F-D10-PadCN5_3)") (class "Default")
      (node (ref "M1") (pin "CN5_3") (pinfunction "D10_CN5_3") (pintype "bidirectional+no_connect"))
    )
    (net (code "138") (name "unconnected-(M1F-D11-PadCN5_4)") (class "Default")
      (node (ref "M1") (pin "CN5_4") (pinfunction "D11_CN5_4") (pintype "bidirectional+no_connect"))
    )
    (net (code "139") (name "unconnected-(M1F-D12-PadCN5_5)") (class "Default")
      (node (ref "M1") (pin "CN5_5") (pinfunction "D12_CN5_5") (pintype "bidirectional+no_connect"))
    )
    (net (code "140") (name "unconnected-(M1F-D13-PadCN5_6)") (class "Default")
      (node (ref "M1") (pin "CN5_6") (pinfunction "D13_CN5_6") (pintype "bidirectional+no_connect"))
    )
    (net (code "141") (name "unconnected-(M1F-D14-PadCN5_9)") (class "Default")
      (node (ref "M1") (pin "CN5_9") (pinfunction "D14_CN5_9") (pintype "bidirectional+no_connect"))
    )
    (net (code "142") (name "unconnected-(M1F-D15-PadCN5_10)") (class "Default")
      (node (ref "M1") (pin "CN5_10") (pinfunction "D15_CN5_10") (pintype "bidirectional+no_connect"))
    )
    (net (code "143") (name "unconnected-(M1F-GND_CN5-PadCN5_7)") (class "Default")
      (node (ref "M1") (pin "CN5_7") (pinfunction "GND_CN5_CN5_7") (pintype "power_in+no_connect"))
    )
    (net (code "144") (name "unconnected-(U5-A7-Pad9)") (class "Default")
      (node (ref "U5") (pin "9") (pinfunction "A7_9") (pintype "passive+no_connect"))
    )
    (net (code "145") (name "unconnected-(U5-A8-Pad10)") (class "Default")
      (node (ref "U5") (pin "10") (pinfunction "A8_10") (pintype "passive+no_connect"))
    )
  )
)
